# 32-178.net
KiCad netlist of a schematic drawn in Altium Designer
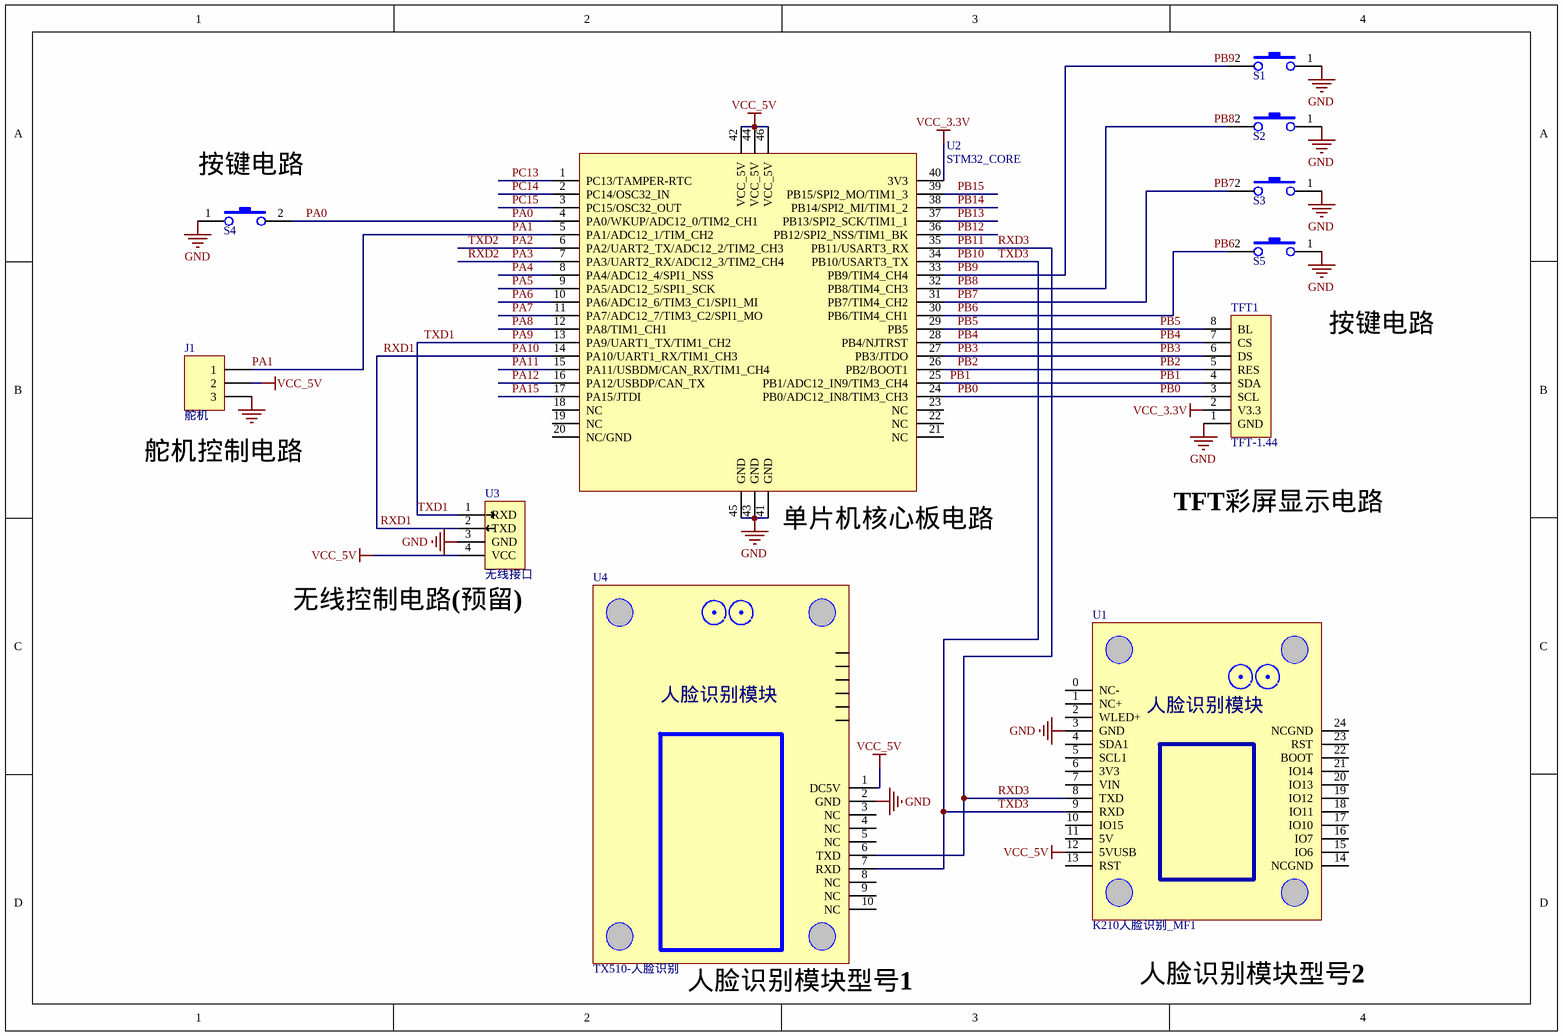
[diagram p0: 32-178原理图（源文件格式）.SchDoc]

(export (version "E")
  (design (tool "Eeschema 10.0.6"))
  (components
    (comp (ref "J1")
      (value "舵机")
      (footprint "TWKJ_S:舵机接口")
      (description "接线端子3芯")
      (fields (field (name "PUBLISHER") "Altium Limited"))
      (libsource (lib "TWKJ_S") (part "CON3"))
    )
    (comp (ref "S1")
      (value "Button")
      (footprint "TWKJ_S:BUTTON_6x6DIP")
      (description "按键")
      (libsource (lib "TWKJ_S") (part "Button"))
    )
    (comp (ref "S2")
      (value "Button")
      (footprint "TWKJ_S:BUTTON_6x6DIP")
      (description "按键")
      (libsource (lib "TWKJ_S") (part "Button"))
    )
    (comp (ref "S3")
      (value "Button")
      (footprint "TWKJ_S:BUTTON_6x6DIP")
      (description "按键")
      (libsource (lib "TWKJ_S") (part "Button"))
    )
    (comp (ref "S4")
      (value "Button")
      (footprint "TWKJ_S:BUTTON_6x6DIP")
      (description "按键")
      (libsource (lib "TWKJ_S") (part "Button"))
    )
    (comp (ref "S5")
      (value "Button")
      (footprint "TWKJ_S:BUTTON_6x6DIP")
      (description "按键")
      (libsource (lib "TWKJ_S") (part "Button"))
    )
    (comp (ref "TFT1") (value "TFT-1.44") (footprint "TFT-1.44") (libsource (lib "TWKJ_S") (part "TFT-1.44")))
    (comp (ref "U1")
      (value "K210人脸识别_MF1")
      (footprint "K210_MF1")
      (libsource (lib "TWKJ_S") (part "K210人脸识别_MF1"))
    )
    (comp (ref "U2")
      (value "STM32_CORE")
      (footprint "TWKJ_S:STM32_CORE")
      (description "STM32核心板")
      (libsource (lib "TWKJ_S") (part "STM32_CORE"))
    )
    (comp (ref "U3")
      (value "无线接口")
      (footprint "TWKJ_S:蓝牙MODE平放")
      (description "蓝牙模块")
      (libsource (lib "TWKJ_S") (part "蓝牙MODE"))
    )
    (comp (ref "U4") (value "TX510-人脸识别") (footprint "TX510") (libsource (lib "TWKJ_S") (part "TX510-人脸识别")))
  )
  (nets
    (net (code "1") (name "/PA0") (class "Default")
      (node (ref "S4") (pin "2") (pinfunction "2_2") (pintype "passive"))
      (node (ref "U2") (pin "4") (pinfunction "PA0/WKUP/ADC12_0/TIM2_CH1_4") (pintype "passive"))
    )
    (net (code "2") (name "/PA1") (class "Default")
      (node (ref "J1") (pin "1") (pinfunction "1_1") (pintype "passive"))
      (node (ref "U2") (pin "5") (pinfunction "PA1/ADC12_1/TIM_CH2_5") (pintype "passive"))
    )
    (net (code "3") (name "/PA2") (class "Default")
      (node (ref "U2") (pin "6") (pinfunction "PA2/UART2_TX/ADC12_2/TIM2_CH3_6") (pintype "passive"))
    )
    (net (code "4") (name "/PA3") (class "Default")
      (node (ref "U2") (pin "7") (pinfunction "PA3/UART2_RX/ADC12_3/TIM2_CH4_7") (pintype "passive"))
    )
    (net (code "5") (name "/PA4") (class "Default")
      (node (ref "U2") (pin "8") (pinfunction "PA4/ADC12_4/SPI1_NSS_8") (pintype "passive"))
    )
    (net (code "6") (name "/PA5") (class "Default")
      (node (ref "U2") (pin "9") (pinfunction "PA5/ADC12_5/SPI1_SCK_9") (pintype "passive"))
    )
    (net (code "7") (name "/PA6") (class "Default")
      (node (ref "U2") (pin "10") (pinfunction "PA6/ADC12_6/TIM3_C1/SPI1_MI_10") (pintype "passive"))
    )
    (net (code "8") (name "/PA7") (class "Default")
      (node (ref "U2") (pin "11") (pinfunction "PA7/ADC12_7/TIM3_C2/SPI1_MO_11") (pintype "passive"))
    )
    (net (code "9") (name "/PA8") (class "Default")
      (node (ref "U2") (pin "12") (pinfunction "PA8/TIM1_CH1_12") (pintype "passive"))
    )
    (net (code "10") (name "/PA9") (class "Default")
      (node (ref "U2") (pin "13") (pinfunction "PA9/UART1_TX/TIM1_CH2_13") (pintype "passive"))
      (node (ref "U3") (pin "1") (pinfunction "RXD_1") (pintype "passive"))
    )
    (net (code "11") (name "/PA10") (class "Default")
      (node (ref "U2") (pin "14") (pinfunction "PA10/UART1_RX/TIM1_CH3_14") (pintype "passive"))
      (node (ref "U3") (pin "2") (pinfunction "TXD_2") (pintype "passive"))
    )
    (net (code "12") (name "/PA11") (class "Default")
      (node (ref "U2") (pin "15") (pinfunction "PA11/USBDM/CAN_RX/TIM1_CH4_15") (pintype "passive"))
    )
    (net (code "13") (name "/PA12") (class "Default")
      (node (ref "U2") (pin "16") (pinfunction "PA12/USBDP/CAN_TX_16") (pintype "passive"))
    )
    (net (code "14") (name "/PA15") (class "Default")
      (node (ref "U2") (pin "17") (pinfunction "PA15/JTDI_17") (pintype "passive"))
    )
    (net (code "15") (name "/PB0") (class "Default")
      (node (ref "TFT1") (pin "3") (pinfunction "SCL_3") (pintype "passive"))
      (node (ref "U2") (pin "24") (pinfunction "PB0/ADC12_IN8/TIM3_CH3_24") (pintype "passive"))
    )
    (net (code "16") (name "/PB1") (class "Default")
      (node (ref "TFT1") (pin "4") (pinfunction "SDA_4") (pintype "passive"))
      (node (ref "U2") (pin "25") (pinfunction "PB1/ADC12_IN9/TIM3_CH4_25") (pintype "passive"))
    )
    (net (code "17") (name "/PB2") (class "Default")
      (node (ref "TFT1") (pin "5") (pinfunction "RES_5") (pintype "passive"))
      (node (ref "U2") (pin "26") (pinfunction "PB2/BOOT1_26") (pintype "passive"))
    )
    (net (code "18") (name "/PB3") (class "Default")
      (node (ref "TFT1") (pin "6") (pinfunction "DS_6") (pintype "passive"))
      (node (ref "U2") (pin "27") (pinfunction "PB3/JTDO_27") (pintype "passive"))
    )
    (net (code "19") (name "/PB4") (class "Default")
      (node (ref "TFT1") (pin "7") (pinfunction "CS_7") (pintype "passive"))
      (node (ref "U2") (pin "28") (pinfunction "PB4/NJTRST_28") (pintype "passive"))
    )
    (net (code "20") (name "/PB5") (class "Default")
      (node (ref "TFT1") (pin "8") (pinfunction "BL_8") (pintype "passive"))
      (node (ref "U2") (pin "29") (pinfunction "PB5_29") (pintype "passive"))
    )
    (net (code "21") (name "/PB6") (class "Default")
      (node (ref "S5") (pin "2") (pinfunction "2_2") (pintype "passive"))
      (node (ref "U2") (pin "30") (pinfunction "PB6/TIM4_CH1_30") (pintype "passive"))
    )
    (net (code "22") (name "/PB7") (class "Default")
      (node (ref "S3") (pin "2") (pinfunction "2_2") (pintype "passive"))
      (node (ref "U2") (pin "31") (pinfunction "PB7/TIM4_CH2_31") (pintype "passive"))
    )
    (net (code "23") (name "/PB8") (class "Default")
      (node (ref "S2") (pin "2") (pinfunction "2_2") (pintype "passive"))
      (node (ref "U2") (pin "32") (pinfunction "PB8/TIM4_CH3_32") (pintype "passive"))
    )
    (net (code "24") (name "/PB9") (class "Default")
      (node (ref "S1") (pin "2") (pinfunction "2_2") (pintype "passive"))
      (node (ref "U2") (pin "33") (pinfunction "PB9/TIM4_CH4_33") (pintype "passive"))
    )
    (net (code "25") (name "/PB10") (class "Default")
      (node (ref "U1") (pin "9") (pinfunction "RXD_9") (pintype "passive"))
      (node (ref "U2") (pin "34") (pinfunction "PB10/USART3_TX_34") (pintype "passive"))
      (node (ref "U4") (pin "7") (pinfunction "RXD_7") (pintype "passive"))
    )
    (net (code "26") (name "/PB11") (class "Default")
      (node (ref "U1") (pin "8") (pinfunction "TXD_8") (pintype "passive"))
      (node (ref "U2") (pin "35") (pinfunction "PB11/USART3_RX_35") (pintype "passive"))
      (node (ref "U4") (pin "6") (pinfunction "TXD_6") (pintype "passive"))
    )
    (net (code "27") (name "/PB12") (class "Default")
      (node (ref "U2") (pin "36") (pinfunction "PB12/SPI2_NSS/TIM1_BK_36") (pintype "passive"))
    )
    (net (code "28") (name "/PB13") (class "Default")
      (node (ref "U2") (pin "37") (pinfunction "PB13/SPI2_SCK/TIM1_1_37") (pintype "passive"))
    )
    (net (code "29") (name "/PB14") (class "Default")
      (node (ref "U2") (pin "38") (pinfunction "PB14/SPI2_MI/TIM1_2_38") (pintype "passive"))
    )
    (net (code "30") (name "/PB15") (class "Default")
      (node (ref "U2") (pin "39") (pinfunction "PB15/SPI2_MO/TIM1_3_39") (pintype "passive"))
    )
    (net (code "31") (name "/PC13") (class "Default")
      (node (ref "U2") (pin "1") (pinfunction "PC13/TAMPER-RTC_1") (pintype "passive"))
    )
    (net (code "32") (name "/PC14") (class "Default")
      (node (ref "U2") (pin "2") (pinfunction "PC14/OSC32_IN_2") (pintype "passive"))
    )
    (net (code "33") (name "/PC15") (class "Default")
      (node (ref "U2") (pin "3") (pinfunction "PC15/OSC32_OUT_3") (pintype "passive"))
    )
    (net (code "34") (name "GND") (class "Default")
      (node (ref "J1") (pin "3") (pinfunction "3_3") (pintype "passive"))
      (node (ref "S1") (pin "1") (pinfunction "1_1") (pintype "passive"))
      (node (ref "S2") (pin "1") (pinfunction "1_1") (pintype "passive"))
      (node (ref "S3") (pin "1") (pinfunction "1_1") (pintype "passive"))
      (node (ref "S4") (pin "1") (pinfunction "1_1") (pintype "passive"))
      (node (ref "S5") (pin "1") (pinfunction "1_1") (pintype "passive"))
      (node (ref "TFT1") (pin "1") (pinfunction "GND_1") (pintype "passive"))
      (node (ref "U1") (pin "3") (pinfunction "GND_3") (pintype "passive"))
      (node (ref "U2") (pin "41") (pinfunction "GND_41") (pintype "passive"))
      (node (ref "U2") (pin "43") (pinfunction "GND_43") (pintype "passive"))
      (node (ref "U2") (pin "45") (pinfunction "GND_45") (pintype "passive"))
      (node (ref "U3") (pin "3") (pinfunction "GND_3") (pintype "passive"))
      (node (ref "U4") (pin "2") (pinfunction "GND_2") (pintype "passive"))
    )
    (net (code "35") (name "VCC_3.3V") (class "Default")
      (node (ref "TFT1") (pin "2") (pinfunction "V3.3_2") (pintype "passive"))
      (node (ref "U2") (pin "40") (pinfunction "3V3_40") (pintype "passive"))
    )
    (net (code "36") (name "VCC_5V") (class "Default")
      (node (ref "J1") (pin "2") (pinfunction "2_2") (pintype "passive"))
      (node (ref "U1") (pin "12") (pinfunction "5VUSB_12") (pintype "passive"))
      (node (ref "U2") (pin "42") (pinfunction "VCC_5V_42") (pintype "passive"))
      (node (ref "U2") (pin "44") (pinfunction "VCC_5V_44") (pintype "passive"))
      (node (ref "U2") (pin "46") (pinfunction "VCC_5V_46") (pintype "passive"))
      (node (ref "U3") (pin "4") (pinfunction "VCC_4") (pintype "passive"))
      (node (ref "U4") (pin "1") (pinfunction "DC5V_1") (pintype "passive"))
    )
    (net (code "37") (name "unconnected-(U1-3V3-Pad6)") (class "Default")
      (node (ref "U1") (pin "6") (pinfunction "3V3_6") (pintype "passive"))
    )
    (net (code "38") (name "unconnected-(U1-5V-Pad11)") (class "Default")
      (node (ref "U1") (pin "11") (pinfunction "5V_11") (pintype "passive"))
    )
    (net (code "39") (name "unconnected-(U1-BOOT-Pad22)") (class "Default")
      (node (ref "U1") (pin "22") (pinfunction "BOOT_22") (pintype "passive"))
    )
    (net (code "40") (name "unconnected-(U1-IO6-Pad15)") (class "Default")
      (node (ref "U1") (pin "15") (pinfunction "IO6_15") (pintype "passive"))
    )
    (net (code "41") (name "unconnected-(U1-IO7-Pad16)") (class "Default")
      (node (ref "U1") (pin "16") (pinfunction "IO7_16") (pintype "passive"))
    )
    (net (code "42") (name "unconnected-(U1-IO10-Pad17)") (class "Default")
      (node (ref "U1") (pin "17") (pinfunction "IO10_17") (pintype "passive"))
    )
    (net (code "43") (name "unconnected-(U1-IO11-Pad18)") (class "Default")
      (node (ref "U1") (pin "18") (pinfunction "IO11_18") (pintype "passive"))
    )
    (net (code "44") (name "unconnected-(U1-IO12-Pad19)") (class "Default")
      (node (ref "U1") (pin "19") (pinfunction "IO12_19") (pintype "passive"))
    )
    (net (code "45") (name "unconnected-(U1-IO13-Pad20)") (class "Default")
      (node (ref "U1") (pin "20") (pinfunction "IO13_20") (pintype "passive"))
    )
    (net (code "46") (name "unconnected-(U1-IO14-Pad21)") (class "Default")
      (node (ref "U1") (pin "21") (pinfunction "IO14_21") (pintype "passive"))
    )
    (net (code "47") (name "unconnected-(U1-IO15-Pad10)") (class "Default")
      (node (ref "U1") (pin "10") (pinfunction "IO15_10") (pintype "passive"))
    )
    (net (code "48") (name "unconnected-(U1-NC+-Pad1)") (class "Default")
      (node (ref "U1") (pin "1") (pinfunction "NC+_1") (pintype "passive"))
    )
    (net (code "49") (name "unconnected-(U1-NC--Pad0)") (class "Default")
      (node (ref "U1") (pin "0") (pinfunction "NC-_0") (pintype "passive"))
    )
    (net (code "50") (name "unconnected-(U1-NCGND-Pad14)") (class "Default")
      (node (ref "U1") (pin "14") (pinfunction "NCGND_14") (pintype "passive"))
    )
    (net (code "51") (name "unconnected-(U1-NCGND-Pad24)") (class "Default")
      (node (ref "U1") (pin "24") (pinfunction "NCGND_24") (pintype "passive"))
    )
    (net (code "52") (name "unconnected-(U1-RST-Pad13)") (class "Default")
      (node (ref "U1") (pin "13") (pinfunction "RST_13") (pintype "passive"))
    )
    (net (code "53") (name "unconnected-(U1-RST-Pad23)") (class "Default")
      (node (ref "U1") (pin "23") (pinfunction "RST_23") (pintype "passive"))
    )
    (net (code "54") (name "unconnected-(U1-SCL1-Pad5)") (class "Default")
      (node (ref "U1") (pin "5") (pinfunction "SCL1_5") (pintype "passive"))
    )
    (net (code "55") (name "unconnected-(U1-SDA1-Pad4)") (class "Default")
      (node (ref "U1") (pin "4") (pinfunction "SDA1_4") (pintype "passive"))
    )
    (net (code "56") (name "unconnected-(U1-VIN-Pad7)") (class "Default")
      (node (ref "U1") (pin "7") (pinfunction "VIN_7") (pintype "passive"))
    )
    (net (code "57") (name "unconnected-(U1-WLED+-Pad2)") (class "Default")
      (node (ref "U1") (pin "2") (pinfunction "WLED+_2") (pintype "passive"))
    )
    (net (code "58") (name "unconnected-(U2-NC-Pad18)") (class "Default")
      (node (ref "U2") (pin "18") (pinfunction "NC_18") (pintype "passive"))
    )
    (net (code "59") (name "unconnected-(U2-NC-Pad19)") (class "Default")
      (node (ref "U2") (pin "19") (pinfunction "NC_19") (pintype "passive"))
    )
    (net (code "60") (name "unconnected-(U2-NC-Pad21)") (class "Default")
      (node (ref "U2") (pin "21") (pinfunction "NC_21") (pintype "passive"))
    )
    (net (code "61") (name "unconnected-(U2-NC-Pad22)") (class "Default")
      (node (ref "U2") (pin "22") (pinfunction "NC_22") (pintype "passive"))
    )
    (net (code "62") (name "unconnected-(U2-NC-Pad23)") (class "Default")
      (node (ref "U2") (pin "23") (pinfunction "NC_23") (pintype "passive"))
    )
    (net (code "63") (name "unconnected-(U2-NC{slash}GND-Pad20)") (class "Default")
      (node (ref "U2") (pin "20") (pinfunction "NC/GND_20") (pintype "passive"))
    )
    (net (code "64") (name "unconnected-(U4-NC-Pad3)") (class "Default")
      (node (ref "U4") (pin "3") (pinfunction "NC_3") (pintype "passive"))
    )
    (net (code "65") (name "unconnected-(U4-NC-Pad4)") (class "Default")
      (node (ref "U4") (pin "4") (pinfunction "NC_4") (pintype "passive"))
    )
    (net (code "66") (name "unconnected-(U4-NC-Pad5)") (class "Default")
      (node (ref "U4") (pin "5") (pinfunction "NC_5") (pintype "passive"))
    )
    (net (code "67") (name "unconnected-(U4-NC-Pad8)") (class "Default")
      (node (ref "U4") (pin "8") (pinfunction "NC_8") (pintype "passive"))
    )
    (net (code "68") (name "unconnected-(U4-NC-Pad9)") (class "Default")
      (node (ref "U4") (pin "9") (pinfunction "NC_9") (pintype "passive"))
    )
    (net (code "69") (name "unconnected-(U4-NC-Pad10)") (class "Default")
      (node (ref "U4") (pin "10") (pinfunction "NC_10") (pintype "passive"))
    )
  )
)
